# tremolo.net
KiCad netlist of a schematic drawn in EAGLE
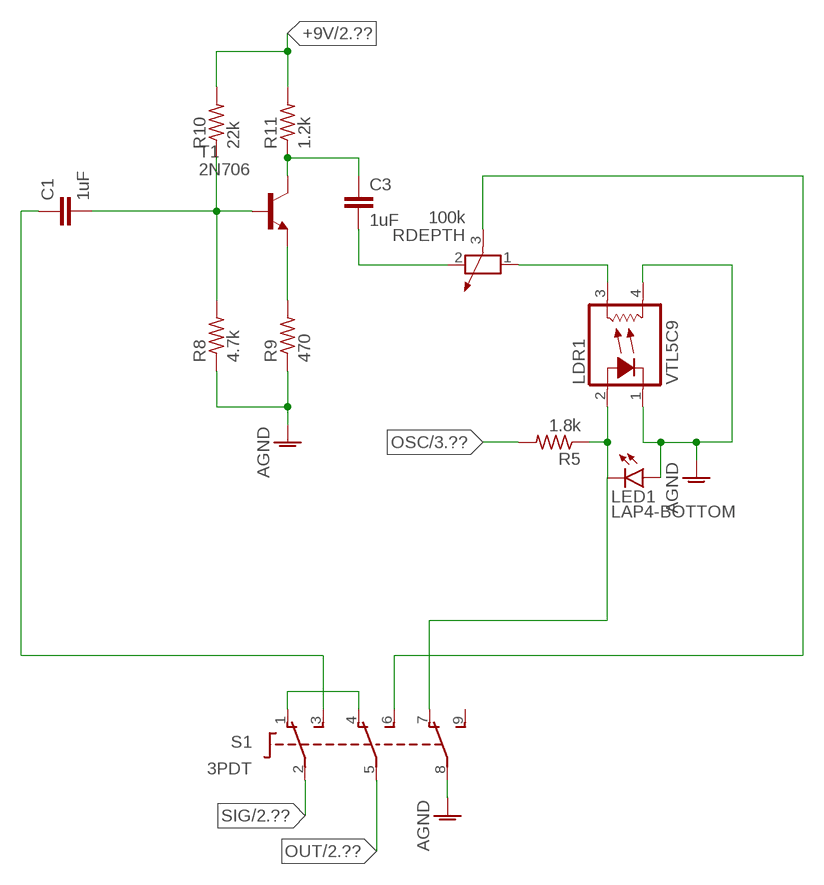
[diagram p0: schematic, sheet 1]
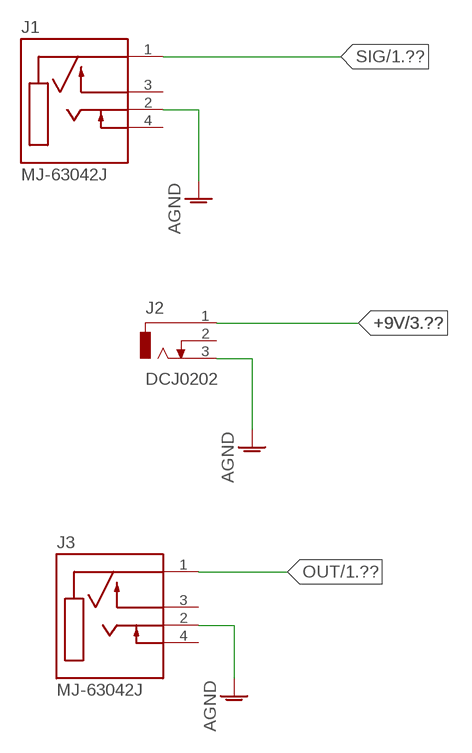
[diagram p1: schematic, sheet 2]
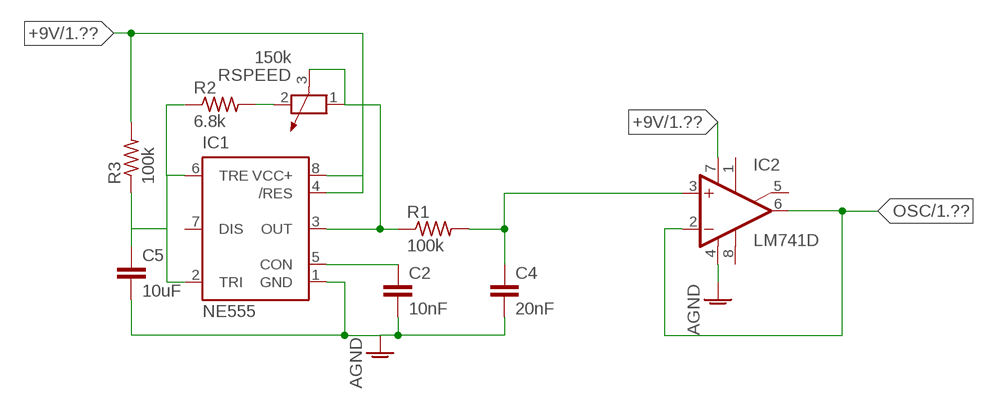
[diagram p2: schematic, sheet 3]

(export (version "E")
  (design (tool "Eeschema 10.0.6"))
  (components
    (comp (ref "J1")
      (value "MJ-63042J")
      (footprint "eagle-import:CUI_MJ-63042J")
      (fields (field (name "MF") "CUI Devices"))
      (libsource (lib "eagle-import") (part "MJ-63042J"))
    )
    (comp (ref "J2")
      (value "DCJ0202")
      (footprint "eagle-import:DCJ0202")
      (fields (field (name "SPICEPREFIX") "M"))
      (libsource (lib "eagle-import") (part "DCJ0202"))
    )
    (comp (ref "J3")
      (value "MJ-63042J")
      (footprint "eagle-import:CUI_MJ-63042J")
      (fields (field (name "MF") "CUI Devices"))
      (libsource (lib "eagle-import") (part "MJ-63042J"))
    )
    (comp (ref "C2")
      (value "10nF")
      (footprint "eagle-import:C025-024X044")
      (libsource (lib "eagle-import") (part "C-EU025-024X044"))
    )
    (comp (ref "C4")
      (value "20nF")
      (footprint "eagle-import:C025-024X044")
      (libsource (lib "eagle-import") (part "C-EU025-024X044"))
    )
    (comp (ref "C5")
      (value "10uF")
      (footprint "eagle-import:C025-024X044")
      (libsource (lib "eagle-import") (part "C-EU025-024X044"))
    )
    (comp (ref "IC1")
      (value "NE555")
      (footprint "eagle-import:DIL-08")
      (fields (field (name "MF") "Arrow Electronics") (field (name "MPN") "NE555N"))
      (libsource (lib "eagle-import") (part "NE555"))
    )
    (comp (ref "IC2")
      (value "LM741D")
      (footprint "eagle-import:SO08")
      (libsource (lib "eagle-import") (part "741DLM"))
    )
    (comp (ref "R1")
      (value "100k")
      (footprint "eagle-import:0204V")
      (libsource (lib "eagle-import") (part "R-US_0204/2V"))
    )
    (comp (ref "R2")
      (value "6.8k")
      (footprint "eagle-import:0204V")
      (libsource (lib "eagle-import") (part "R-US_0204/2V"))
    )
    (comp (ref "R3")
      (value "100k")
      (footprint "eagle-import:0204V")
      (libsource (lib "eagle-import") (part "R-US_0204/2V"))
    )
    (comp (ref "RSPEED")
      (value "150k")
      (footprint "eagle-import:PT-10")
      (libsource (lib "eagle-import") (part "POTENTIOMETER_PT-10"))
    )
    (comp (ref "C1")
      (value "1uF")
      (footprint "eagle-import:C025-024X044")
      (libsource (lib "eagle-import") (part "C-EU025-024X044"))
    )
    (comp (ref "C3")
      (value "1uF")
      (footprint "eagle-import:C025-024X044")
      (libsource (lib "eagle-import") (part "C-EU025-024X044"))
    )
    (comp (ref "LDR1")
      (value "VTL5C9")
      (footprint "eagle-import:VTL5C")
      (fields (field (name "MF") "VACTEC PHOTO"))
      (libsource (lib "eagle-import") (part "VTL5C9"))
    )
    (comp (ref "LED1")
      (value "LAP4-BOTTOM")
      (footprint "eagle-import:P47F-BOTTOM")
      (libsource (lib "eagle-import") (part "P4-BOTTOMLA"))
    )
    (comp (ref "R5")
      (value "1.8k")
      (footprint "eagle-import:0204V")
      (libsource (lib "eagle-import") (part "R-US_0204/2V"))
    )
    (comp (ref "R8")
      (value "4.7k")
      (footprint "eagle-import:0204V")
      (libsource (lib "eagle-import") (part "R-US_0204/2V"))
    )
    (comp (ref "R9")
      (value "470")
      (footprint "eagle-import:0204V")
      (libsource (lib "eagle-import") (part "R-US_0204/2V"))
    )
    (comp (ref "R10")
      (value "22k")
      (footprint "eagle-import:0204V")
      (libsource (lib "eagle-import") (part "R-US_0204/2V"))
    )
    (comp (ref "R11")
      (value "1.2k")
      (footprint "eagle-import:0204V")
      (libsource (lib "eagle-import") (part "R-US_0204/2V"))
    )
    (comp (ref "RDEPTH")
      (value "100k")
      (footprint "eagle-import:PT-10")
      (libsource (lib "eagle-import") (part "POTENTIOMETER_PT-10"))
    )
    (comp (ref "S1")
      (value "3PDT")
      (footprint "eagle-import:3PDT")
      (libsource (lib "eagle-import") (part "3PDT"))
    )
    (comp (ref "T1")
      (value "2N706")
      (footprint "eagle-import:TO18")
      (libsource (lib "eagle-import") (part "2N706"))
    )
  )
  (nets
    (net (code "1") (name "+9V") (class "Default")
      (node (ref "IC1") (pin "4") (pinfunction "/RES_4") (pintype "input"))
      (node (ref "IC1") (pin "8") (pinfunction "VCC+_8") (pintype "power_in"))
      (node (ref "IC2") (pin "7") (pinfunction "V+_7") (pintype "power_in"))
      (node (ref "J2") (pin "1") (pinfunction "1_1") (pintype "passive"))
      (node (ref "R10") (pin "2") (pinfunction "2_2") (pintype "passive"))
      (node (ref "R11") (pin "2") (pinfunction "2_2") (pintype "passive"))
      (node (ref "R3") (pin "2") (pinfunction "2_2") (pintype "passive"))
    )
    (net (code "2") (name "AGND") (class "Default")
      (node (ref "C2") (pin "2") (pinfunction "2_2") (pintype "passive"))
      (node (ref "C4") (pin "2") (pinfunction "2_2") (pintype "passive"))
      (node (ref "C5") (pin "2") (pinfunction "2_2") (pintype "passive"))
      (node (ref "IC1") (pin "1") (pinfunction "GND_1") (pintype "power_in"))
      (node (ref "IC2") (pin "4") (pinfunction "V-_4") (pintype "power_in"))
      (node (ref "J1") (pin "2") (pinfunction "TIP_2") (pintype "passive"))
      (node (ref "J2") (pin "3") (pinfunction "3_3") (pintype "passive"))
      (node (ref "J3") (pin "2") (pinfunction "TIP_2") (pintype "passive"))
      (node (ref "LDR1") (pin "1") (pinfunction "C_1") (pintype "passive"))
      (node (ref "LDR1") (pin "4") (pinfunction "L2_4") (pintype "passive"))
      (node (ref "LED1") (pin "A") (pinfunction "A_A") (pintype "passive"))
      (node (ref "R8") (pin "1") (pinfunction "1_1") (pintype "passive"))
      (node (ref "R9") (pin "1") (pinfunction "1_1") (pintype "passive"))
      (node (ref "S1") (pin "8") (pinfunction "P3_8") (pintype "passive"))
    )
    (net (code "3") (name "EFX") (class "Default")
      (node (ref "C3") (pin "1") (pinfunction "1_1") (pintype "passive"))
      (node (ref "R11") (pin "1") (pinfunction "1_1") (pintype "passive"))
      (node (ref "RDEPTH") (pin "3") (pinfunction "3_3") (pintype "passive"))
      (node (ref "S1") (pin "6") (pinfunction "S2_6") (pintype "passive"))
      (node (ref "T1") (pin "3") (pinfunction "C_3") (pintype "passive"))
    )
    (net (code "4") (name "Net-(C3-Pad2)") (class "Default")
      (node (ref "C3") (pin "2") (pinfunction "2_2") (pintype "passive"))
      (node (ref "RDEPTH") (pin "2") (pinfunction "2_2") (pintype "passive"))
    )
    (net (code "5") (name "Net-(IC1-CON)") (class "Default")
      (node (ref "C2") (pin "1") (pinfunction "1_1") (pintype "passive"))
      (node (ref "IC1") (pin "5") (pinfunction "CON_5") (pintype "input"))
    )
    (net (code "6") (name "Net-(IC1-OUT)") (class "Default")
      (node (ref "IC1") (pin "3") (pinfunction "OUT_3") (pintype "output"))
      (node (ref "R1") (pin "1") (pinfunction "1_1") (pintype "passive"))
      (node (ref "RSPEED") (pin "1") (pinfunction "1_1") (pintype "passive"))
      (node (ref "RSPEED") (pin "3") (pinfunction "3_3") (pintype "passive"))
    )
    (net (code "7") (name "Net-(IC1-TRE)") (class "Default")
      (node (ref "C5") (pin "1") (pinfunction "1_1") (pintype "passive"))
      (node (ref "IC1") (pin "2") (pinfunction "TRI_2") (pintype "input"))
      (node (ref "IC1") (pin "6") (pinfunction "TRE_6") (pintype "input"))
      (node (ref "R2") (pin "1") (pinfunction "1_1") (pintype "passive"))
      (node (ref "R3") (pin "1") (pinfunction "1_1") (pintype "passive"))
    )
    (net (code "8") (name "Net-(IC2-+IN)") (class "Default")
      (node (ref "C4") (pin "1") (pinfunction "1_1") (pintype "passive"))
      (node (ref "IC2") (pin "3") (pinfunction "+IN_3") (pintype "input"))
      (node (ref "R1") (pin "2") (pinfunction "2_2") (pintype "passive"))
    )
    (net (code "9") (name "Net-(LDR1-A)") (class "Default")
      (node (ref "LDR1") (pin "2") (pinfunction "A_2") (pintype "passive"))
      (node (ref "LED1") (pin "C") (pinfunction "C_C") (pintype "passive"))
      (node (ref "R5") (pin "1") (pinfunction "1_1") (pintype "passive"))
      (node (ref "S1") (pin "7") (pinfunction "O3_7") (pintype "passive"))
    )
    (net (code "10") (name "Net-(LDR1-L1)") (class "Default")
      (node (ref "LDR1") (pin "3") (pinfunction "L1_3") (pintype "passive"))
      (node (ref "RDEPTH") (pin "1") (pinfunction "1_1") (pintype "passive"))
    )
    (net (code "11") (name "Net-(R2-Pad2)") (class "Default")
      (node (ref "R2") (pin "2") (pinfunction "2_2") (pintype "passive"))
      (node (ref "RSPEED") (pin "2") (pinfunction "2_2") (pintype "passive"))
    )
    (net (code "12") (name "Net-(S1-O1)") (class "Default")
      (node (ref "S1") (pin "1") (pinfunction "O1_1") (pintype "passive"))
      (node (ref "S1") (pin "4") (pinfunction "O2_4") (pintype "passive"))
    )
    (net (code "13") (name "Net-(S1-S1)") (class "Default")
      (node (ref "C1") (pin "1") (pinfunction "1_1") (pintype "passive"))
      (node (ref "S1") (pin "3") (pinfunction "S1_3") (pintype "passive"))
    )
    (net (code "14") (name "Net-(T1-B)") (class "Default")
      (node (ref "C1") (pin "2") (pinfunction "2_2") (pintype "passive"))
      (node (ref "R10") (pin "1") (pinfunction "1_1") (pintype "passive"))
      (node (ref "R8") (pin "2") (pinfunction "2_2") (pintype "passive"))
      (node (ref "T1") (pin "2") (pinfunction "B_2") (pintype "passive"))
    )
    (net (code "15") (name "Net-(T1-E)") (class "Default")
      (node (ref "R9") (pin "2") (pinfunction "2_2") (pintype "passive"))
      (node (ref "T1") (pin "1") (pinfunction "E_1") (pintype "passive"))
    )
    (net (code "16") (name "OSC") (class "Default")
      (node (ref "IC2") (pin "2") (pinfunction "-IN_2") (pintype "input"))
      (node (ref "IC2") (pin "6") (pinfunction "OUT_6") (pintype "output"))
      (node (ref "R5") (pin "2") (pinfunction "2_2") (pintype "passive"))
    )
    (net (code "17") (name "OUT") (class "Default")
      (node (ref "J3") (pin "1") (pinfunction "SLEEVE_1") (pintype "passive"))
      (node (ref "S1") (pin "5") (pinfunction "P2_5") (pintype "passive"))
    )
    (net (code "18") (name "SIG") (class "Default")
      (node (ref "J1") (pin "1") (pinfunction "SLEEVE_1") (pintype "passive"))
      (node (ref "S1") (pin "2") (pinfunction "P1_2") (pintype "passive"))
    )
    (net (code "19") (name "unconnected-(IC1-DIS-Pad7)") (class "Default")
      (node (ref "IC1") (pin "7") (pinfunction "DIS_7") (pintype "input"))
    )
    (net (code "20") (name "unconnected-(IC2-ON1-Pad1)") (class "Default")
      (node (ref "IC2") (pin "1") (pinfunction "ON1_1") (pintype "passive"))
    )
    (net (code "21") (name "unconnected-(IC2-ON2-Pad5)") (class "Default")
      (node (ref "IC2") (pin "5") (pinfunction "ON2_5") (pintype "passive"))
    )
    (net (code "22") (name "unconnected-(IC2-OPT-Pad8)") (class "Default")
      (node (ref "IC2") (pin "8") (pinfunction "OPT_8") (pintype "passive"))
    )
    (net (code "23") (name "unconnected-(J1-SLEEVE_SWITCH-Pad3)") (class "Default")
      (node (ref "J1") (pin "3") (pinfunction "SLEEVE_SWITCH_3") (pintype "passive"))
    )
    (net (code "24") (name "unconnected-(J1-TIP_SWITCH-Pad4)") (class "Default")
      (node (ref "J1") (pin "4") (pinfunction "TIP_SWITCH_4") (pintype "passive"))
    )
    (net (code "25") (name "unconnected-(J2-Pad2)") (class "Default")
      (node (ref "J2") (pin "2") (pinfunction "2_2") (pintype "passive"))
    )
    (net (code "26") (name "unconnected-(J3-SLEEVE_SWITCH-Pad3)") (class "Default")
      (node (ref "J3") (pin "3") (pinfunction "SLEEVE_SWITCH_3") (pintype "passive"))
    )
    (net (code "27") (name "unconnected-(J3-TIP_SWITCH-Pad4)") (class "Default")
      (node (ref "J3") (pin "4") (pinfunction "TIP_SWITCH_4") (pintype "passive"))
    )
    (net (code "28") (name "unconnected-(S1-S3-Pad9)") (class "Default")
      (node (ref "S1") (pin "9") (pinfunction "S3_9") (pintype "passive"))
    )
  )
)
